# ADC.net
KiCad netlist of a schematic drawn in Altium Designer
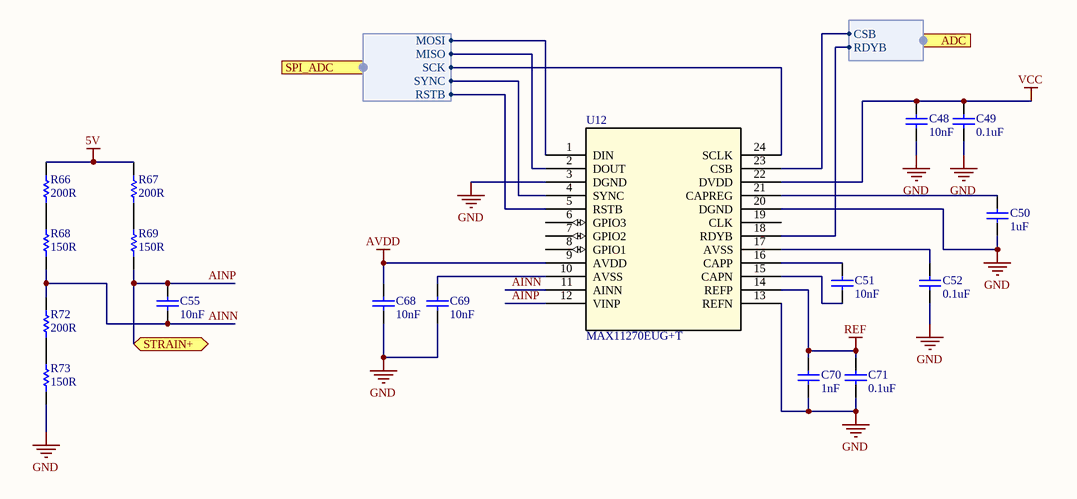
[diagram p0: ADC.SchDoc]

(export (version "E")
  (design (tool "Eeschema 10.0.6"))
  (components
    (comp (ref "C48")
      (value "10nF")
      (footprint "C0603[1608X92]")
      (description "10nF 6.3V 10% 0603 (1608 Metric)")
      (fields (field (name "PARTNUMBER") "GRM188R70J103KA01D") (field (name "MANUFACTURER") "Murata"))
      (libsource (lib "Capacitors") (part "CAP_10nF_6.3V_0603_10%"))
    )
    (comp (ref "C49")
      (value "0.1uF")
      (footprint "C0603[1608X92]")
      (description "0.1uF 6.3V 10% 0603 (1608 Metric)")
      (fields (field (name "PARTNUMBER") "GRM188R70J104KA01D") (field (name "MANUFACTURER") "Murata"))
      (libsource (lib "Capacitors") (part "CAP_0.1uF_6.3V_0603_10%"))
    )
    (comp (ref "C50")
      (value "1uF")
      (footprint "C0603[1608X92]")
      (description "1uF 6.3V 10% 0603 (1608 Metric)")
      (fields (field (name "PARTNUMBER") "GRM188R60J105KA01D") (field (name "MANUFACTURER") "Murata"))
      (libsource (lib "Capacitors") (part "CAP_1uF_6.3V_0603_10%"))
    )
    (comp (ref "C51")
      (value "10nF")
      (footprint "C0603[1608X92]")
      (description "10nF 6.3V 10% 0603 (1608 Metric)")
      (fields (field (name "PARTNUMBER") "GRM188R70J103KA01D") (field (name "MANUFACTURER") "Murata"))
      (libsource (lib "Capacitors") (part "CAP_10nF_6.3V_0603_10%"))
    )
    (comp (ref "C52")
      (value "0.1uF")
      (footprint "C0603[1608X92]")
      (description "0.1uF 6.3V 10% 0603 (1608 Metric)")
      (fields (field (name "PARTNUMBER") "GRM188R70J104KA01D") (field (name "MANUFACTURER") "Murata"))
      (libsource (lib "Capacitors") (part "CAP_0.1uF_6.3V_0603_10%"))
    )
    (comp (ref "C55")
      (value "10nF")
      (footprint "C0603[1608X92]")
      (description "10nF 6.3V 10% 0603 (1608 Metric)")
      (fields (field (name "PARTNUMBER") "GRM188R70J103KA01D") (field (name "MANUFACTURER") "Murata"))
      (libsource (lib "Capacitors") (part "CAP_10nF_6.3V_0603_10%"))
    )
    (comp (ref "C68")
      (value "10nF")
      (footprint "C0603[1608X92]")
      (description "10nF 6.3V 10% 0603 (1608 Metric)")
      (fields (field (name "PARTNUMBER") "GRM188R70J103KA01D") (field (name "MANUFACTURER") "Murata"))
      (libsource (lib "Capacitors") (part "CAP_10nF_6.3V_0603_10%"))
    )
    (comp (ref "C69")
      (value "10nF")
      (footprint "C0603[1608X92]")
      (description "10nF 6.3V 10% 0603 (1608 Metric)")
      (fields (field (name "PARTNUMBER") "GRM188R70J103KA01D") (field (name "MANUFACTURER") "Murata"))
      (libsource (lib "Capacitors") (part "CAP_10nF_6.3V_0603_10%"))
    )
    (comp (ref "C70")
      (value "1nF")
      (footprint "C0603[1608X92]")
      (description "1nF 6.3V 5% 0603 (1608 Metric)")
      (fields (field (name "PARTNUMBER") "GRM1885C1H102JA01D") (field (name "MANUFACTURER") "Murata"))
      (libsource (lib "Capacitors") (part "CAP_1nF_6.3V_0603_5%"))
    )
    (comp (ref "C71")
      (value "0.1uF")
      (footprint "C0603[1608X92]")
      (description "0.1uF 6.3V 10% 0603 (1608 Metric)")
      (fields (field (name "PARTNUMBER") "GRM188R70J104KA01D") (field (name "MANUFACTURER") "Murata"))
      (libsource (lib "Capacitors") (part "CAP_0.1uF_6.3V_0603_10%"))
    )
    (comp (ref "R66")
      (value "200R")
      (footprint "R0603[1608]")
      (description "200R 0.25W 1% 0603 (1005 Metric)")
      (fields (field (name "MANUFACTURER") "Vishay / Dale") (field (name "PARTNUMBER") "CRCW0603200RFKEAHP"))
      (libsource (lib "Resistors") (part "RES_200R_0603_1%"))
    )
    (comp (ref "R67")
      (value "200R")
      (footprint "R0603[1608]")
      (description "200R 0.25W 1% 0603 (1005 Metric)")
      (fields (field (name "MANUFACTURER") "Vishay / Dale") (field (name "PARTNUMBER") "CRCW0603200RFKEAHP"))
      (libsource (lib "Resistors") (part "RES_200R_0603_1%"))
    )
    (comp (ref "R68")
      (value "150R")
      (footprint "R0603[1608]")
      (description "150R 0.25W 1% 0603 (1005 Metric)")
      (fields (field (name "MANUFACTURER") "Vishay / Dale") (field (name "PARTNUMBER") "CRCW0603150RFKEAHP"))
      (libsource (lib "Resistors") (part "RES_150R_0603_1%"))
    )
    (comp (ref "R69")
      (value "150R")
      (footprint "R0603[1608]")
      (description "150R 0.25W 1% 0603 (1005 Metric)")
      (fields (field (name "MANUFACTURER") "Vishay / Dale") (field (name "PARTNUMBER") "CRCW0603150RFKEAHP"))
      (libsource (lib "Resistors") (part "RES_150R_0603_1%"))
    )
    (comp (ref "R72")
      (value "200R")
      (footprint "R0603[1608]")
      (description "200R 0.25W 1% 0603 (1005 Metric)")
      (fields (field (name "MANUFACTURER") "Vishay / Dale") (field (name "PARTNUMBER") "CRCW0603200RFKEAHP"))
      (libsource (lib "Resistors") (part "RES_200R_0603_1%"))
    )
    (comp (ref "R73")
      (value "150R")
      (footprint "R0603[1608]")
      (description "150R 0.25W 1% 0603 (1005 Metric)")
      (fields (field (name "MANUFACTURER") "Vishay / Dale") (field (name "PARTNUMBER") "CRCW0603150RFKEAHP"))
      (libsource (lib "Resistors") (part "RES_150R_0603_1%"))
    )
    (comp (ref "U12")
      (value "MAX11270EUG+T")
      (footprint "21-0066J_24")
      (description "Imported")
      (fields (field (name "PARTNUMBER") "MAX111270EUG+T") (field (name "MANUFACTURER") "Maxim"))
      (libsource (lib "General_Component") (part "MAX11270EUG+T"))
    )
  )
  (nets
    (net (code "3") (name "/AINN") (class "Default")
      (node (ref "C55") (pin "1") (pinfunction "1_1") (pintype "passive"))
      (node (ref "R68") (pin "1") (pinfunction "1_1") (pintype "passive"))
      (node (ref "R72") (pin "2") (pinfunction "2_2") (pintype "passive"))
      (node (ref "U12") (pin "11") (pinfunction "AINN_11") (pintype "passive"))
    )
    (net (code "4") (name "/AINP") (class "Default")
      (node (ref "C55") (pin "2") (pinfunction "2_2") (pintype "passive"))
      (node (ref "R69") (pin "1") (pinfunction "1_1") (pintype "passive"))
      (node (ref "U12") (pin "12") (pinfunction "VINP_12") (pintype "passive"))
    )
    (net (code "5") (name "/CSB") (class "Default")
      (node (ref "U12") (pin "23") (pinfunction "CSB_23") (pintype "passive"))
    )
    (net (code "6") (name "/MISO") (class "Default")
      (node (ref "U12") (pin "2") (pinfunction "DOUT_2") (pintype "passive"))
    )
    (net (code "7") (name "/MOSI") (class "Default")
      (node (ref "U12") (pin "1") (pinfunction "DIN_1") (pintype "passive"))
    )
    (net (code "8") (name "/RDYB") (class "Default")
      (node (ref "U12") (pin "18") (pinfunction "RDYB_18") (pintype "passive"))
    )
    (net (code "9") (name "/RSTB") (class "Default")
      (node (ref "U12") (pin "5") (pinfunction "RSTB_5") (pintype "passive"))
    )
    (net (code "10") (name "/SCK") (class "Default")
      (node (ref "U12") (pin "24") (pinfunction "SCLK_24") (pintype "passive"))
    )
    (net (code "11") (name "/SYNC") (class "Default")
      (node (ref "U12") (pin "4") (pinfunction "SYNC_4") (pintype "passive"))
    )
    (net (code "14") (name "5V") (class "Default")
      (node (ref "R66") (pin "2") (pinfunction "2_2") (pintype "passive"))
      (node (ref "R67") (pin "2") (pinfunction "2_2") (pintype "passive"))
    )
    (net (code "15") (name "AVDD") (class "Default")
      (node (ref "C68") (pin "2") (pinfunction "2_2") (pintype "passive"))
      (node (ref "U12") (pin "9") (pinfunction "AVDD_9") (pintype "power_in"))
    )
    (net (code "16") (name "GND") (class "Default")
      (node (ref "C48") (pin "1") (pinfunction "1_1") (pintype "passive"))
      (node (ref "C49") (pin "1") (pinfunction "1_1") (pintype "passive"))
      (node (ref "C50") (pin "1") (pinfunction "1_1") (pintype "passive"))
      (node (ref "C52") (pin "1") (pinfunction "1_1") (pintype "passive"))
      (node (ref "C68") (pin "1") (pinfunction "1_1") (pintype "passive"))
      (node (ref "C69") (pin "1") (pinfunction "1_1") (pintype "passive"))
      (node (ref "C70") (pin "1") (pinfunction "1_1") (pintype "passive"))
      (node (ref "C71") (pin "1") (pinfunction "1_1") (pintype "passive"))
      (node (ref "R73") (pin "1") (pinfunction "1_1") (pintype "passive"))
      (node (ref "U12") (pin "13") (pinfunction "REFN_13") (pintype "passive"))
      (node (ref "U12") (pin "20") (pinfunction "DGND_20") (pintype "power_in"))
      (node (ref "U12") (pin "3") (pinfunction "DGND_3") (pintype "power_in"))
    )
    (net (code "17") (name "Net-(C52-Pad2)") (class "Default")
      (node (ref "C52") (pin "2") (pinfunction "2_2") (pintype "passive"))
      (node (ref "U12") (pin "17") (pinfunction "AVSS_17") (pintype "power_in"))
    )
    (net (code "18") (name "Net-(C69-Pad2)") (class "Default")
      (node (ref "C69") (pin "2") (pinfunction "2_2") (pintype "passive"))
      (node (ref "U12") (pin "10") (pinfunction "AVSS_10") (pintype "power_in"))
    )
    (net (code "19") (name "Net-(R66-Pad1)") (class "Default")
      (node (ref "R66") (pin "1") (pinfunction "1_1") (pintype "passive"))
      (node (ref "R68") (pin "2") (pinfunction "2_2") (pintype "passive"))
    )
    (net (code "20") (name "Net-(R67-Pad1)") (class "Default")
      (node (ref "R67") (pin "1") (pinfunction "1_1") (pintype "passive"))
      (node (ref "R69") (pin "2") (pinfunction "2_2") (pintype "passive"))
    )
    (net (code "21") (name "Net-(R72-Pad1)") (class "Default")
      (node (ref "R72") (pin "1") (pinfunction "1_1") (pintype "passive"))
      (node (ref "R73") (pin "2") (pinfunction "2_2") (pintype "passive"))
    )
    (net (code "22") (name "Net-(U12-CAPN)") (class "Default")
      (node (ref "C51") (pin "1") (pinfunction "1_1") (pintype "passive"))
      (node (ref "U12") (pin "15") (pinfunction "CAPN_15") (pintype "passive"))
    )
    (net (code "23") (name "Net-(U12-CAPP)") (class "Default")
      (node (ref "C51") (pin "2") (pinfunction "2_2") (pintype "passive"))
      (node (ref "U12") (pin "16") (pinfunction "CAPP_16") (pintype "passive"))
    )
    (net (code "24") (name "Net-(U12-CAPREG)") (class "Default")
      (node (ref "C50") (pin "2") (pinfunction "2_2") (pintype "passive"))
      (node (ref "U12") (pin "21") (pinfunction "CAPREG_21") (pintype "power_in"))
    )
    (net (code "25") (name "REF") (class "Default")
      (node (ref "C70") (pin "2") (pinfunction "2_2") (pintype "passive"))
      (node (ref "C71") (pin "2") (pinfunction "2_2") (pintype "passive"))
      (node (ref "U12") (pin "14") (pinfunction "REFP_14") (pintype "passive"))
    )
    (net (code "26") (name "VCC") (class "Default")
      (node (ref "C48") (pin "2") (pinfunction "2_2") (pintype "passive"))
      (node (ref "C49") (pin "2") (pinfunction "2_2") (pintype "passive"))
      (node (ref "U12") (pin "22") (pinfunction "DVDD_22") (pintype "power_in"))
    )
    (net (code "27") (name "unconnected-(U12-CLK-Pad19)") (class "Default")
      (node (ref "U12") (pin "19") (pinfunction "CLK_19") (pintype "passive"))
    )
    (net (code "28") (name "unconnected-(U12-GPIO1-Pad8)") (class "Default")
      (node (ref "U12") (pin "8") (pinfunction "GPIO1_8") (pintype "bidirectional"))
    )
    (net (code "29") (name "unconnected-(U12-GPIO2-Pad7)") (class "Default")
      (node (ref "U12") (pin "7") (pinfunction "GPIO2_7") (pintype "bidirectional"))
    )
    (net (code "30") (name "unconnected-(U12-GPIO3-Pad6)") (class "Default")
      (node (ref "U12") (pin "6") (pinfunction "GPIO3_6") (pintype "bidirectional"))
    )
  )
)
